# Sheet6.net
KiCad netlist of a schematic drawn in Altium Designer
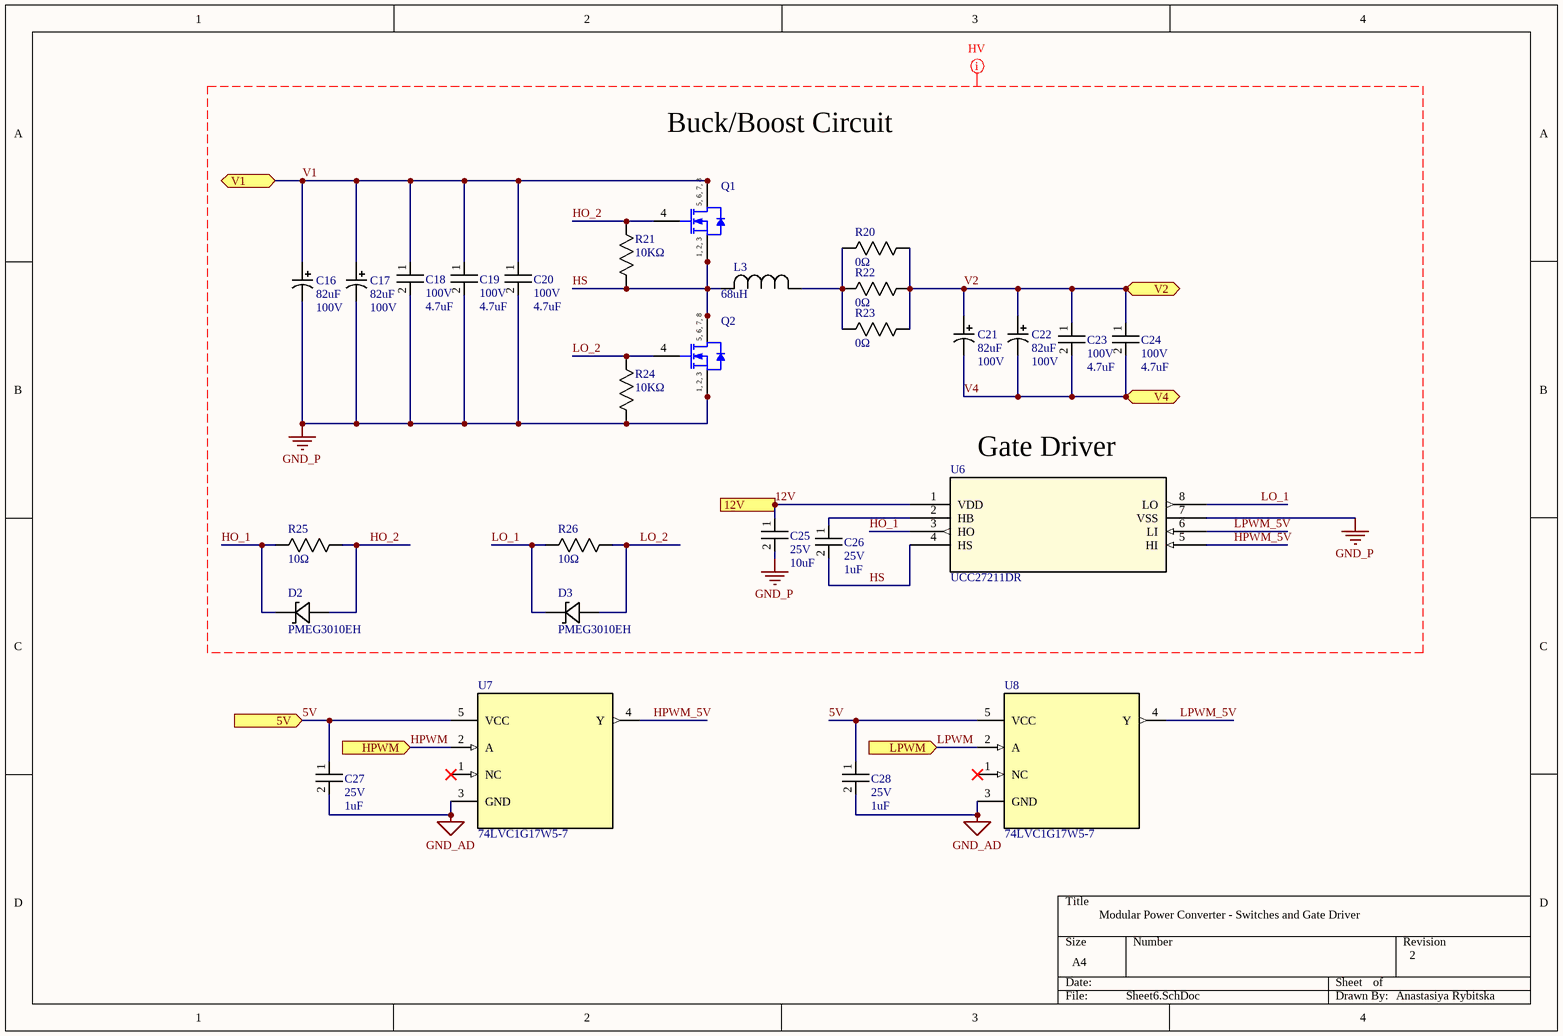
[diagram p0: Sheet6.SchDoc]

(export (version "E")
  (design (tool "Eeschema 10.0.6"))
  (components
    (comp (ref "C16")
      (value "100ZLJ82M10X16")
      (footprint "CAP_YX_10X16_RUB")
      (description "No Description Available")
      (fields
        (field (name "CAPACITANCE") "82uF")
        (field (name "VOLTAGE RATING") "100V")
        (field (name "COPYRIGHT") "Copyright (C) 2022 Ultra Librarian. All rights reserved.")
      )
      (libsource (lib "100ZLJ82M10X16") (part "100ZLJ82M10X16"))
    )
    (comp (ref "C17")
      (value "100ZLJ82M10X16")
      (footprint "CAP_YX_10X16_RUB")
      (description "No Description Available")
      (fields
        (field (name "CAPACITANCE") "82uF")
        (field (name "VOLTAGE RATING") "100V")
        (field (name "COPYRIGHT") "Copyright (C) 2022 Ultra Librarian. All rights reserved.")
      )
      (libsource (lib "100ZLJ82M10X16") (part "100ZLJ82M10X16"))
    )
    (comp (ref "C18")
      (value "C2012X5R2A475K125AC")
      (footprint "0805")
      (description "CAP CER 4.7UF 100V X5R 0805")
      (fields (field (name "VOLTAGE RATING") "100V") (field (name "CAPACITANCE") "4.7uF"))
      (libsource (lib "Schlib1") (part "GRM21BD72A225ME01L"))
    )
    (comp (ref "C19")
      (value "C2012X5R2A475K125AC")
      (footprint "0805")
      (description "CAP CER 4.7UF 100V X5R 0805")
      (fields (field (name "VOLTAGE RATING") "100V") (field (name "CAPACITANCE") "4.7uF"))
      (libsource (lib "Schlib1") (part "GRM21BD72A225ME01L"))
    )
    (comp (ref "C20")
      (value "C2012X5R2A475K125AC")
      (footprint "0805")
      (description "CAP CER 4.7UF 100V X5R 0805")
      (fields (field (name "VOLTAGE RATING") "100V") (field (name "CAPACITANCE") "4.7uF"))
      (libsource (lib "Schlib1") (part "GRM21BD72A225ME01L"))
    )
    (comp (ref "C21")
      (value "100ZLJ82M10X16")
      (footprint "CAP_YX_10X16_RUB")
      (description "No Description Available")
      (fields
        (field (name "CAPACITANCE") "82uF")
        (field (name "VOLTAGE RATING") "100V")
        (field (name "COPYRIGHT") "Copyright (C) 2022 Ultra Librarian. All rights reserved.")
      )
      (libsource (lib "100ZLJ82M10X16") (part "100ZLJ82M10X16"))
    )
    (comp (ref "C22")
      (value "100ZLJ82M10X16")
      (footprint "CAP_YX_10X16_RUB")
      (description "No Description Available")
      (fields
        (field (name "CAPACITANCE") "82uF")
        (field (name "VOLTAGE RATING") "100V")
        (field (name "COPYRIGHT") "Copyright (C) 2022 Ultra Librarian. All rights reserved.")
      )
      (libsource (lib "100ZLJ82M10X16") (part "100ZLJ82M10X16"))
    )
    (comp (ref "C23")
      (value "GRM21BD72A225ME01L")
      (footprint "0805")
      (description "CAP CER 2.2UF 100V X7T 0805")
      (fields (field (name "VOLTAGE RATING") "100V") (field (name "CAPACITANCE") "4.7uF"))
      (libsource (lib "Schlib1") (part "GRM21BD72A225ME01L"))
    )
    (comp (ref "C24")
      (value "GRM21BD72A225ME01L")
      (footprint "0805")
      (description "CAP CER 2.2UF 100V X7T 0805")
      (fields (field (name "VOLTAGE RATING") "100V") (field (name "CAPACITANCE") "4.7uF"))
      (libsource (lib "Schlib1") (part "GRM21BD72A225ME01L"))
    )
    (comp (ref "C25")
      (value "TMK212BBJ106KG-T")
      (footprint "0805")
      (description "Multilayer Ceramic Capacitor 10uF 25V X5R 10% SMD 0805 T/R")
      (fields (field (name "VOLTAGE RATING") "25V") (field (name "CAPACITANCE") "10uF"))
      (libsource (lib "Schlib1") (part "TMK212BBJ106KG-T"))
    )
    (comp (ref "C26")
      (value "CL10B105KA8NFNC")
      (footprint "0603")
      (description "Cap Ceramic 1uF 25V X7R ±10% Pad SMD 0603 +125°C T/R")
      (fields (field (name "VOLTAGE RATING") "25V") (field (name "CAPACITANCE") "1uF"))
      (libsource (lib "Schlib1") (part "CL10B105KA8NFNC"))
    )
    (comp (ref "C27")
      (value "CL10B105KA8NFNC")
      (footprint "0603")
      (description "Cap Ceramic 1uF 25V X7R ±10% Pad SMD 0603 +125°C T/R")
      (fields (field (name "VOLTAGE RATING") "25V") (field (name "CAPACITANCE") "1uF"))
      (libsource (lib "Schlib1") (part "CL10B105KA8NFNC"))
    )
    (comp (ref "C28")
      (value "CL10B105KA8NFNC")
      (footprint "0603")
      (description "Cap Ceramic 1uF 25V X7R ±10% Pad SMD 0603 +125°C T/R")
      (fields (field (name "VOLTAGE RATING") "25V") (field (name "CAPACITANCE") "1uF"))
      (libsource (lib "Schlib1") (part "CL10B105KA8NFNC"))
    )
    (comp (ref "D2")
      (value "PMEG3010EH")
      (footprint "SOD123F_NXP")
      (description "No Description Available")
      (fields (field (name "COPYRIGHT") "Copyright (C) 2022 Ultra Librarian. All rights reserved."))
      (libsource (lib "PMEG3010EH") (part "PMEG3010EH"))
    )
    (comp (ref "D3")
      (value "PMEG3010EH")
      (footprint "SOD123F_NXP")
      (description "No Description Available")
      (fields (field (name "COPYRIGHT") "Copyright (C) 2022 Ultra Librarian. All rights reserved."))
      (libsource (lib "PMEG3010EH") (part "PMEG3010EH"))
    )
    (comp (ref "L3")
      (value "PA4349.683ANLT")
      (footprint "IND_PA4349.683ANLT_PUL")
      (description "No Description Available")
      (fields
        (field (name "INDUCTANCE") "68uH")
        (field (name "COPYRIGHT") "Copyright (C) 2022 Ultra Librarian. All rights reserved.")
      )
      (libsource (lib "PA4349.683ANLT") (part "PA4349.683ANLT"))
    )
    (comp (ref "Q1")
      (value "TPH9R00CQH,LQ")
      (footprint "INF-PG-TDSON-8-1_V")
      (description "N-Channel 150 V 64A (Tc) 960mW (Ta), 210W (Tc) Surface Mount 8-SOP Advance (5x5)")
      (fields (field (name "MANUFACTURER") "Infineon") (field (name "PARTNUMBER") "BSC240N12NS3 G"))
      (libsource (lib "Altium Content Vault") (part "INF-NEMOS-SSSGDDDD-8"))
    )
    (comp (ref "Q2")
      (value "TPH9R00CQH,LQ")
      (footprint "INF-PG-TDSON-8-1_V")
      (description "N-Channel 150 V 64A (Tc) 960mW (Ta), 210W (Tc) Surface Mount 8-SOP Advance (5x5)")
      (fields (field (name "MANUFACTURER") "Infineon") (field (name "PARTNUMBER") "BSC240N12NS3 G"))
      (libsource (lib "Altium Content Vault") (part "INF-NEMOS-SSSGDDDD-8"))
    )
    (comp (ref "R20")
      (value "AC0603FR-070RL")
      (footprint "0603")
      (description "RES SMD 0 OHM JUMPER 1/10W 0603")
      (fields (field (name "RESISTANCE") "0Ω"))
      (libsource (lib "Schlib1") (part "AC0603FR-070RL"))
    )
    (comp (ref "R21")
      (value "RNCP0603FTD10K0")
      (footprint "0603")
      (description "10kΩ ±1% 0.125W 0603 High Power Anti-Sulfur Thin Film Chip Resistor")
      (fields (field (name "RESISTANCE") "10KΩ"))
      (libsource (lib "Schlib1") (part "RNCP0603FTD10K0"))
    )
    (comp (ref "R22")
      (value "AC0603FR-070RL")
      (footprint "0603")
      (description "RES SMD 0 OHM JUMPER 1/10W 0603")
      (fields (field (name "RESISTANCE") "0Ω"))
      (libsource (lib "Schlib1") (part "AC0603FR-070RL"))
    )
    (comp (ref "R23")
      (value "AC0603FR-070RL")
      (footprint "0603")
      (description "RES SMD 0 OHM JUMPER 1/10W 0603")
      (fields (field (name "RESISTANCE") "0Ω"))
      (libsource (lib "Schlib1") (part "AC0603FR-070RL"))
    )
    (comp (ref "R24")
      (value "RNCP0603FTD10K0")
      (footprint "0603")
      (description "10kΩ ±1% 0.125W 0603 High Power Anti-Sulfur Thin Film Chip Resistor")
      (fields (field (name "RESISTANCE") "10KΩ"))
      (libsource (lib "Schlib1") (part "RNCP0603FTD10K0"))
    )
    (comp (ref "R25")
      (value "RMCF0603JT10R0")
      (footprint "0603")
      (description "RES 10 OHM 5% 1/10W 0603")
      (fields (field (name "RESISTANCE") "10Ω"))
      (libsource (lib "Schlib1") (part "RMCF0603JT10R0"))
    )
    (comp (ref "R26")
      (value "RMCF0603JT10R0")
      (footprint "0603")
      (description "RES 10 OHM 5% 1/10W 0603")
      (fields (field (name "RESISTANCE") "10Ω"))
      (libsource (lib "Schlib1") (part "RMCF0603JT10R0"))
    )
    (comp (ref "U6")
      (value "UCC27211DR")
      (footprint "D8")
      (description "IC GATE DRVR HALF-BRIDGE 8SOIC")
      (fields
        (field (name "MANUFACTURER_PART_NUMBER") "UCC27210D")
        (field (name "COPYRIGHT") "Copyright (C) 2022 Ultra Librarian. All rights reserved.")
      )
      (libsource (lib "UCC27210D") (part "UCC27210D"))
    )
    (comp (ref "U7")
      (value "74LVC1G17W5-7")
      (footprint "SOT95P280X145-5N")
      (description "Buffer, Non-Inverting 1 Element 1 Bit per Element Push-Pull Output SOT-25")
      (fields (field (name "DIGI-KEY_PART_NUMBER") "74LVC1G17W5-7CT-ND") (field (name "MF") "Diodes Inc."))
      (libsource (lib "74LVC1G17W5-7") (part "74LVC1G17W5-7"))
    )
    (comp (ref "U8")
      (value "74LVC1G17W5-7")
      (footprint "SOT95P280X145-5N")
      (description "Buffer, Non-Inverting 1 Element 1 Bit per Element Push-Pull Output SOT-25")
      (fields (field (name "DIGI-KEY_PART_NUMBER") "74LVC1G17W5-7CT-ND") (field (name "MF") "Diodes Inc."))
      (libsource (lib "74LVC1G17W5-7") (part "74LVC1G17W5-7"))
    )
  )
  (nets
    (net (code "1") (name "/5V") (class "Default")
      (node (ref "C27") (pin "1") (pinfunction "1_1") (pintype "passive"))
      (node (ref "C28") (pin "1") (pinfunction "1_1") (pintype "passive"))
      (node (ref "U7") (pin "5") (pinfunction "VCC_5") (pintype "passive"))
      (node (ref "U8") (pin "5") (pinfunction "VCC_5") (pintype "passive"))
    )
    (net (code "2") (name "/12V") (class "Default")
      (node (ref "C25") (pin "1") (pinfunction "1_1") (pintype "passive"))
      (node (ref "U6") (pin "1") (pinfunction "VDD_1") (pintype "passive"))
    )
    (net (code "3") (name "/HO_1") (class "Default")
      (node (ref "D2") (pin "1") (pinfunction "1_1") (pintype "passive"))
      (node (ref "R25") (pin "1") (pinfunction "1_1") (pintype "passive"))
      (node (ref "U6") (pin "3") (pinfunction "HO_3") (pintype "output"))
    )
    (net (code "4") (name "/HO_2") (class "Default")
      (node (ref "D2") (pin "2") (pinfunction "2_2") (pintype "passive"))
      (node (ref "Q1") (pin "4") (pinfunction "GATE_4") (pintype "passive"))
      (node (ref "R21") (pin "2") (pinfunction "2_2") (pintype "passive"))
      (node (ref "R25") (pin "2") (pinfunction "2_2") (pintype "passive"))
    )
    (net (code "5") (name "/HPWM") (class "Default")
      (node (ref "U7") (pin "2") (pinfunction "A_2") (pintype "input"))
    )
    (net (code "6") (name "/HPWM_5V") (class "Default")
      (node (ref "U6") (pin "5") (pinfunction "HI_5") (pintype "input"))
      (node (ref "U7") (pin "4") (pinfunction "Y_4") (pintype "output"))
    )
    (net (code "7") (name "/HS") (class "Default")
      (node (ref "C26") (pin "2") (pinfunction "2_2") (pintype "passive"))
      (node (ref "L3") (pin "2") (pinfunction "2_2") (pintype "passive"))
      (node (ref "Q1") (pin "1") (pinfunction "SOURCE_1") (pintype "passive"))
      (node (ref "Q1") (pin "2") (pinfunction "SOURCE_2") (pintype "passive"))
      (node (ref "Q1") (pin "3") (pinfunction "SOURCE_3") (pintype "passive"))
      (node (ref "Q2") (pin "5") (pinfunction "DRAIN_5") (pintype "passive"))
      (node (ref "Q2") (pin "6") (pinfunction "DRAIN_6") (pintype "passive"))
      (node (ref "Q2") (pin "7") (pinfunction "DRAIN_7") (pintype "passive"))
      (node (ref "Q2") (pin "8") (pinfunction "DRAIN_8") (pintype "passive"))
      (node (ref "R21") (pin "1") (pinfunction "1_1") (pintype "passive"))
      (node (ref "U6") (pin "4") (pinfunction "HS_4") (pintype "passive"))
    )
    (net (code "8") (name "/LO_1") (class "Default")
      (node (ref "D3") (pin "1") (pinfunction "1_1") (pintype "passive"))
      (node (ref "R26") (pin "1") (pinfunction "1_1") (pintype "passive"))
      (node (ref "U6") (pin "8") (pinfunction "LO_8") (pintype "output"))
    )
    (net (code "9") (name "/LO_2") (class "Default")
      (node (ref "D3") (pin "2") (pinfunction "2_2") (pintype "passive"))
      (node (ref "Q2") (pin "4") (pinfunction "GATE_4") (pintype "passive"))
      (node (ref "R24") (pin "2") (pinfunction "2_2") (pintype "passive"))
      (node (ref "R26") (pin "2") (pinfunction "2_2") (pintype "passive"))
    )
    (net (code "10") (name "/LPWM") (class "Default")
      (node (ref "U8") (pin "2") (pinfunction "A_2") (pintype "input"))
    )
    (net (code "11") (name "/LPWM_5V") (class "Default")
      (node (ref "U6") (pin "6") (pinfunction "LI_6") (pintype "input"))
      (node (ref "U8") (pin "4") (pinfunction "Y_4") (pintype "output"))
    )
    (net (code "12") (name "/V1") (class "Default")
      (node (ref "C16") (pin "1") (pinfunction "1_1") (pintype "passive"))
      (node (ref "C17") (pin "1") (pinfunction "1_1") (pintype "passive"))
      (node (ref "C18") (pin "1") (pinfunction "1_1") (pintype "passive"))
      (node (ref "C19") (pin "1") (pinfunction "1_1") (pintype "passive"))
      (node (ref "C20") (pin "1") (pinfunction "1_1") (pintype "passive"))
      (node (ref "Q1") (pin "5") (pinfunction "DRAIN_5") (pintype "passive"))
      (node (ref "Q1") (pin "6") (pinfunction "DRAIN_6") (pintype "passive"))
      (node (ref "Q1") (pin "7") (pinfunction "DRAIN_7") (pintype "passive"))
      (node (ref "Q1") (pin "8") (pinfunction "DRAIN_8") (pintype "passive"))
    )
    (net (code "13") (name "/V2") (class "Default")
      (node (ref "C21") (pin "1") (pinfunction "1_1") (pintype "passive"))
      (node (ref "C22") (pin "1") (pinfunction "1_1") (pintype "passive"))
      (node (ref "C23") (pin "1") (pinfunction "1_1") (pintype "passive"))
      (node (ref "C24") (pin "1") (pinfunction "1_1") (pintype "passive"))
      (node (ref "R20") (pin "2") (pinfunction "2_2") (pintype "passive"))
      (node (ref "R22") (pin "2") (pinfunction "2_2") (pintype "passive"))
      (node (ref "R23") (pin "2") (pinfunction "2_2") (pintype "passive"))
    )
    (net (code "14") (name "/V4") (class "Default")
      (node (ref "C21") (pin "2") (pinfunction "2_2") (pintype "passive"))
      (node (ref "C22") (pin "2") (pinfunction "2_2") (pintype "passive"))
      (node (ref "C23") (pin "2") (pinfunction "2_2") (pintype "passive"))
      (node (ref "C24") (pin "2") (pinfunction "2_2") (pintype "passive"))
    )
    (net (code "15") (name "GND_AD") (class "Default")
      (node (ref "C27") (pin "2") (pinfunction "2_2") (pintype "passive"))
      (node (ref "C28") (pin "2") (pinfunction "2_2") (pintype "passive"))
      (node (ref "U7") (pin "3") (pinfunction "GND_3") (pintype "passive"))
      (node (ref "U8") (pin "3") (pinfunction "GND_3") (pintype "passive"))
    )
    (net (code "16") (name "GND_P") (class "Default")
      (node (ref "C16") (pin "2") (pinfunction "2_2") (pintype "passive"))
      (node (ref "C17") (pin "2") (pinfunction "2_2") (pintype "passive"))
      (node (ref "C18") (pin "2") (pinfunction "2_2") (pintype "passive"))
      (node (ref "C19") (pin "2") (pinfunction "2_2") (pintype "passive"))
      (node (ref "C20") (pin "2") (pinfunction "2_2") (pintype "passive"))
      (node (ref "C25") (pin "2") (pinfunction "2_2") (pintype "passive"))
      (node (ref "Q2") (pin "1") (pinfunction "SOURCE_1") (pintype "passive"))
      (node (ref "Q2") (pin "2") (pinfunction "SOURCE_2") (pintype "passive"))
      (node (ref "Q2") (pin "3") (pinfunction "SOURCE_3") (pintype "passive"))
      (node (ref "R24") (pin "1") (pinfunction "1_1") (pintype "passive"))
      (node (ref "U6") (pin "7") (pinfunction "VSS_7") (pintype "power_in"))
    )
    (net (code "17") (name "Net-(L3-Pad1)") (class "Default")
      (node (ref "L3") (pin "1") (pinfunction "1_1") (pintype "passive"))
      (node (ref "R20") (pin "1") (pinfunction "1_1") (pintype "passive"))
      (node (ref "R22") (pin "1") (pinfunction "1_1") (pintype "passive"))
      (node (ref "R23") (pin "1") (pinfunction "1_1") (pintype "passive"))
    )
    (net (code "18") (name "Net-(U6-HB)") (class "Default")
      (node (ref "C26") (pin "1") (pinfunction "1_1") (pintype "passive"))
      (node (ref "U6") (pin "2") (pinfunction "HB_2") (pintype "passive"))
    )
    (net (code "19") (name "unconnected-(U7-NC-Pad1)") (class "Default")
      (node (ref "U7") (pin "1") (pinfunction "NC_1") (pintype "input+no_connect"))
    )
    (net (code "20") (name "unconnected-(U8-NC-Pad1)") (class "Default")
      (node (ref "U8") (pin "1") (pinfunction "NC_1") (pintype "input+no_connect"))
    )
  )
)
